# USB_OTG_FS.net
KiCad netlist of a schematic drawn in Altium Designer
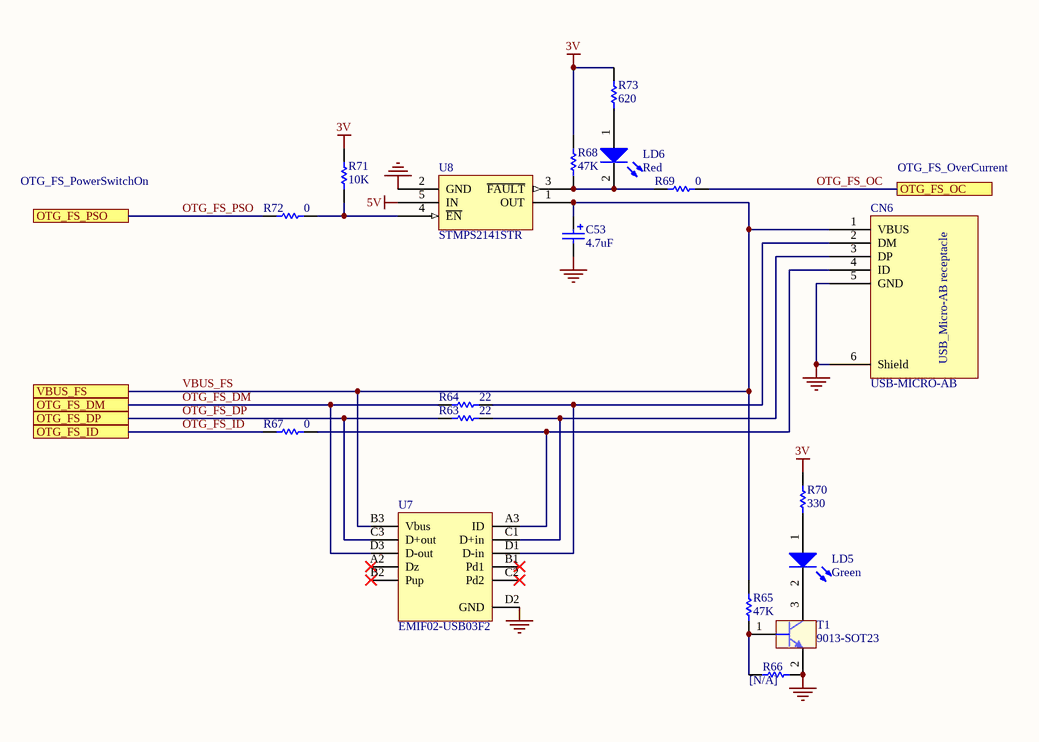
[diagram p0: USB_OTG_FS.SchDoc]

(export (version "E")
  (design (tool "Eeschema 10.0.6"))
  (components
    (comp (ref "C53")
      (value "4.7uF")
      (footprint "TAN-A")
      (description "Polarized Capacitor (Radial)")
      (fields (field (name "PUBLISHER") "Altium Limited"))
      (libsource (lib "Miscellaneous Devices") (part "Cap Pol1"))
    )
    (comp (ref "CN6")
      (value "USB-MICRO-AB")
      (footprint "CON_USBMICROAB_MOLEX_47590-0001_H3")
      (description "USB-MICRO-AB, 47590-0001, SMT, MOLEX")
      (libsource (lib "MCD_TOOLS") (part "USB-MICRO-AB"))
    )
    (comp (ref "LD5")
      (value "Green")
      (footprint "0603D")
      (description "Typical RED, GREEN, YELLOW, AMBER GaAs LED")
      (fields (field (name "PUBLISHER") "Altium Limited"))
      (libsource (lib "Miscellaneous Devices") (part "LED2"))
    )
    (comp (ref "LD6")
      (value "Red")
      (footprint "0603D")
      (description "Typical RED, GREEN, YELLOW, AMBER GaAs LED")
      (fields (field (name "PUBLISHER") "Altium Limited"))
      (libsource (lib "Miscellaneous Devices") (part "LED2"))
    )
    (comp (ref "R63")
      (value "22")
      (footprint "0402R")
      (description "Resistor 0402 / 0603 / 0805")
      (libsource (lib "MCD_TOOLS") (part "Resistor_ST"))
    )
    (comp (ref "R64")
      (value "22")
      (footprint "0402R")
      (description "Resistor 0402 / 0603 / 0805")
      (libsource (lib "MCD_TOOLS") (part "Resistor_ST"))
    )
    (comp (ref "R65")
      (value "47K")
      (footprint "0402R")
      (description "Resistor 0402 / 0603 / 0805")
      (libsource (lib "MCD_TOOLS") (part "Resistor_ST"))
    )
    (comp (ref "R66")
      (value "[N/A]")
      (footprint "0402R")
      (description "Resistor 0402 / 0603 / 0805")
      (libsource (lib "MCD_TOOLS") (part "Resistor_ST"))
    )
    (comp (ref "R67")
      (value "0")
      (footprint "0402R")
      (description "Resistor 0402 / 0603 / 0805")
      (libsource (lib "MCD_TOOLS") (part "Resistor_ST"))
    )
    (comp (ref "R68")
      (value "47K")
      (footprint "0402R")
      (description "Resistor 0402 / 0603 / 0805")
      (libsource (lib "MCD_TOOLS") (part "Resistor_ST"))
    )
    (comp (ref "R69")
      (value "0")
      (footprint "0402R")
      (description "Resistor 0402 / 0603 / 0805")
      (libsource (lib "MCD_TOOLS") (part "Resistor_ST"))
    )
    (comp (ref "R70")
      (value "330")
      (footprint "0603R")
      (description "Resistor 0402 / 0603 / 0805")
      (libsource (lib "MCD_TOOLS") (part "Resistor_ST"))
    )
    (comp (ref "R71")
      (value "10K")
      (footprint "0402R")
      (description "Resistor 0402 / 0603 / 0805")
      (libsource (lib "MCD_TOOLS") (part "Resistor_ST"))
    )
    (comp (ref "R72")
      (value "0")
      (footprint "0402R")
      (description "Resistor 0402 / 0603 / 0805")
      (libsource (lib "MCD_TOOLS") (part "Resistor_ST"))
    )
    (comp (ref "R73")
      (value "620")
      (footprint "0603R")
      (description "Resistor 0402 / 0603 / 0805")
      (libsource (lib "MCD_TOOLS") (part "Resistor_ST"))
    )
    (comp (ref "T1")
      (value "9013-SOT23")
      (footprint "SOT-23")
      (description "NPN Bipolar Transistor")
      (libsource (lib "MCD_TOOLS") (part "9013-SOT23"))
    )
    (comp (ref "U7")
      (value "EMIF02-USB03F2")
      (footprint "Flip Chip")
      (description "2-line IPAD, EMI filter including ESD protection")
      (libsource (lib "MCD_TOOLS") (part "EMIF02-USB03F2"))
    )
    (comp (ref "U8")
      (value "STMPS2141STR")
      (footprint "SOT23-5L")
      (description "Enhanced single channel power switches")
      (libsource (lib "MCD_TOOLS") (part "STMPS2141STR"))
    )
  )
  (nets
    (net (code "1") (name "/OTG_FS_DM") (class "Default")
      (node (ref "R64") (pin "1") (pinfunction "1_1") (pintype "passive"))
      (node (ref "U7") (pin "D3") (pinfunction "D-out_D3") (pintype "passive"))
    )
    (net (code "2") (name "/OTG_FS_DP") (class "Default")
      (node (ref "R63") (pin "1") (pinfunction "1_1") (pintype "passive"))
      (node (ref "U7") (pin "C3") (pinfunction "D+out_C3") (pintype "passive"))
    )
    (net (code "3") (name "/OTG_FS_ID") (class "Default")
      (node (ref "R67") (pin "1") (pinfunction "1_1") (pintype "passive"))
    )
    (net (code "4") (name "/OTG_FS_OC") (class "Default")
      (node (ref "R69") (pin "2") (pinfunction "2_2") (pintype "passive"))
    )
    (net (code "5") (name "/OTG_FS_PSO") (class "Default")
      (node (ref "R72") (pin "1") (pinfunction "1_1") (pintype "passive"))
    )
    (net (code "6") (name "/VBUS_FS") (class "Default")
      (node (ref "C53") (pin "1") (pinfunction "1_1") (pintype "passive"))
      (node (ref "CN6") (pin "1") (pinfunction "VBUS_1") (pintype "passive"))
      (node (ref "R65") (pin "2") (pinfunction "2_2") (pintype "passive"))
      (node (ref "U7") (pin "B3") (pinfunction "Vbus_B3") (pintype "passive"))
      (node (ref "U8") (pin "1") (pinfunction "OUT_1") (pintype "passive"))
    )
    (net (code "7") (name "3V") (class "Default")
      (node (ref "R68") (pin "2") (pinfunction "2_2") (pintype "passive"))
      (node (ref "R70") (pin "2") (pinfunction "2_2") (pintype "passive"))
      (node (ref "R71") (pin "2") (pinfunction "2_2") (pintype "passive"))
      (node (ref "R73") (pin "2") (pinfunction "2_2") (pintype "passive"))
    )
    (net (code "8") (name "5V") (class "Default")
      (node (ref "U8") (pin "5") (pinfunction "IN_5") (pintype "passive"))
    )
    (net (code "9") (name "GND") (class "Default")
      (node (ref "C53") (pin "2") (pinfunction "2_2") (pintype "passive"))
      (node (ref "CN6") (pin "5") (pinfunction "GND_5") (pintype "passive"))
      (node (ref "CN6") (pin "6") (pinfunction "Shield_6") (pintype "passive"))
      (node (ref "R66") (pin "2") (pinfunction "2_2") (pintype "passive"))
      (node (ref "T1") (pin "2") (pinfunction "E_2") (pintype "passive"))
      (node (ref "U7") (pin "D2") (pinfunction "GND_D2") (pintype "passive"))
      (node (ref "U8") (pin "2") (pinfunction "GND_2") (pintype "passive"))
    )
    (net (code "10") (name "Net-(CN6-DM)") (class "Default")
      (node (ref "CN6") (pin "2") (pinfunction "DM_2") (pintype "passive"))
      (node (ref "R64") (pin "2") (pinfunction "2_2") (pintype "passive"))
      (node (ref "U7") (pin "D1") (pinfunction "D-in_D1") (pintype "passive"))
    )
    (net (code "11") (name "Net-(CN6-DP)") (class "Default")
      (node (ref "CN6") (pin "3") (pinfunction "DP_3") (pintype "passive"))
      (node (ref "R63") (pin "2") (pinfunction "2_2") (pintype "passive"))
      (node (ref "U7") (pin "C1") (pinfunction "D+in_C1") (pintype "passive"))
    )
    (net (code "12") (name "Net-(CN6-ID)") (class "Default")
      (node (ref "CN6") (pin "4") (pinfunction "ID_4") (pintype "passive"))
      (node (ref "R67") (pin "2") (pinfunction "2_2") (pintype "passive"))
      (node (ref "U7") (pin "A3") (pinfunction "ID_A3") (pintype "passive"))
    )
    (net (code "13") (name "Net-(LD5-A)") (class "Default")
      (node (ref "LD5") (pin "1") (pinfunction "A_1") (pintype "passive"))
      (node (ref "R70") (pin "1") (pinfunction "1_1") (pintype "passive"))
    )
    (net (code "14") (name "Net-(LD5-K)") (class "Default")
      (node (ref "LD5") (pin "2") (pinfunction "K_2") (pintype "passive"))
      (node (ref "T1") (pin "3") (pinfunction "C_3") (pintype "passive"))
    )
    (net (code "15") (name "Net-(LD6-A)") (class "Default")
      (node (ref "LD6") (pin "1") (pinfunction "A_1") (pintype "passive"))
      (node (ref "R73") (pin "1") (pinfunction "1_1") (pintype "passive"))
    )
    (net (code "16") (name "Net-(LD6-K)") (class "Default")
      (node (ref "LD6") (pin "2") (pinfunction "K_2") (pintype "passive"))
      (node (ref "R68") (pin "1") (pinfunction "1_1") (pintype "passive"))
      (node (ref "R69") (pin "1") (pinfunction "1_1") (pintype "passive"))
      (node (ref "U8") (pin "3") (pinfunction "~{FAULT}_3") (pintype "output"))
    )
    (net (code "17") (name "Net-(T1-B)") (class "Default")
      (node (ref "R65") (pin "1") (pinfunction "1_1") (pintype "passive"))
      (node (ref "R66") (pin "1") (pinfunction "1_1") (pintype "passive"))
      (node (ref "T1") (pin "1") (pinfunction "B_1") (pintype "passive"))
    )
    (net (code "18") (name "Net-(U8-~{EN})") (class "Default")
      (node (ref "R71") (pin "1") (pinfunction "1_1") (pintype "passive"))
      (node (ref "R72") (pin "2") (pinfunction "2_2") (pintype "passive"))
      (node (ref "U8") (pin "4") (pinfunction "~{EN}_4") (pintype "input"))
    )
    (net (code "19") (name "unconnected-(U7-Dz-PadA2)") (class "Default")
      (node (ref "U7") (pin "A2") (pinfunction "Dz_A2") (pintype "passive+no_connect"))
    )
    (net (code "20") (name "unconnected-(U7-Pd1-PadB1)") (class "Default")
      (node (ref "U7") (pin "B1") (pinfunction "Pd1_B1") (pintype "passive+no_connect"))
    )
    (net (code "21") (name "unconnected-(U7-Pd2-PadC2)") (class "Default")
      (node (ref "U7") (pin "C2") (pinfunction "Pd2_C2") (pintype "passive+no_connect"))
    )
    (net (code "22") (name "unconnected-(U7-Pup-PadB2)") (class "Default")
      (node (ref "U7") (pin "B2") (pinfunction "Pup_B2") (pintype "passive+no_connect"))
    )
  )
)
